# atmega328_programmer_V2.net
KiCad netlist of a schematic drawn in EAGLE
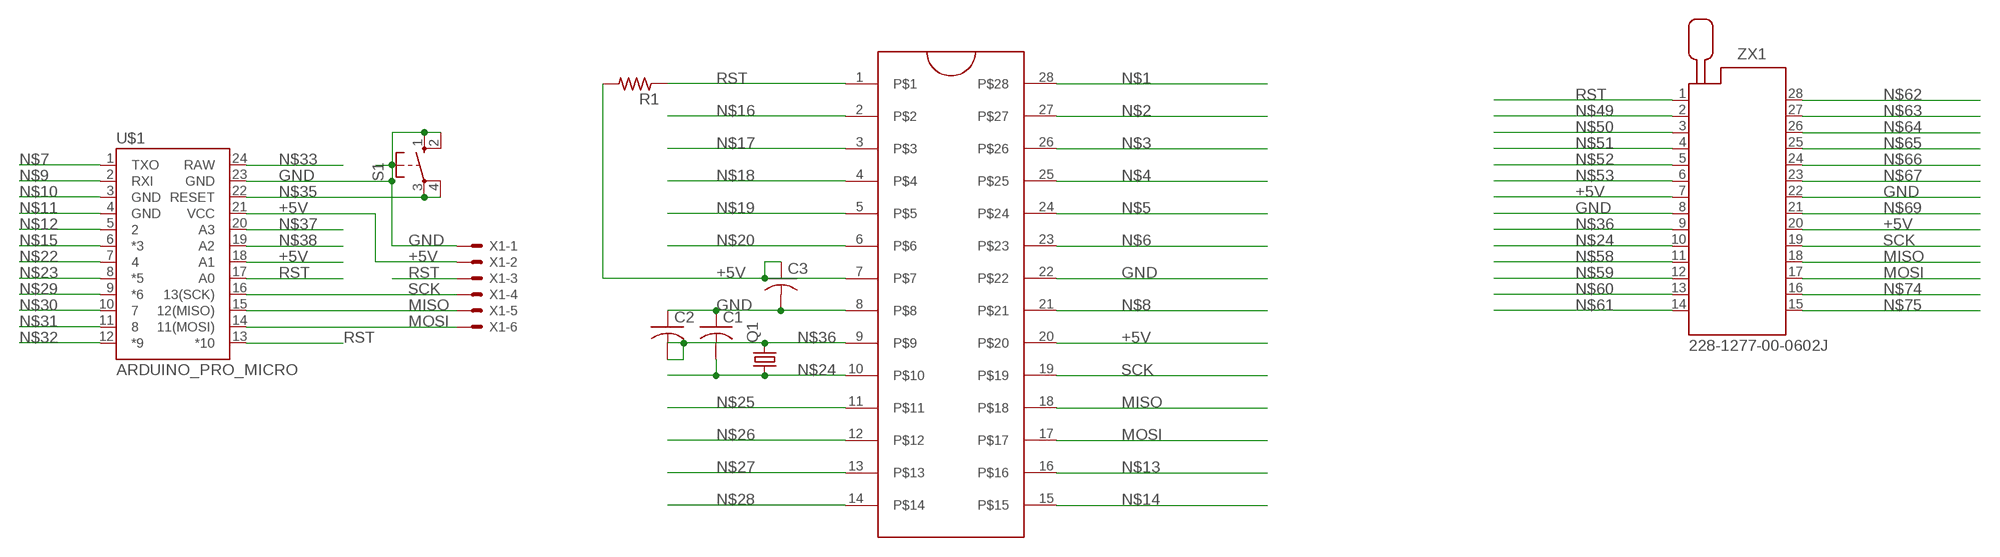
[diagram p0: schematic, sheet 1]

(export (version "E")
  (design (tool "Eeschema 10.0.6"))
  (components
    (comp (ref "C1")
      (value "C-US025-024X044")
      (footprint "eagle-import:C025-024X044")
      (libsource (lib "eagle-import") (part "C-US025-024X044"))
    )
    (comp (ref "C2")
      (value "C-US025-024X044")
      (footprint "eagle-import:C025-024X044")
      (libsource (lib "eagle-import") (part "C-US025-024X044"))
    )
    (comp (ref "C3")
      (value "C-US025-024X044")
      (footprint "eagle-import:C025-024X044")
      (libsource (lib "eagle-import") (part "C-US025-024X044"))
    )
    (comp (ref "Q1")
      (value "CRYSTALHC49U-V")
      (footprint "eagle-import:HC49U-V")
      (libsource (lib "eagle-import") (part "CRYSTALHC49U-V"))
    )
    (comp (ref "R1")
      (value "R-US_0207/10")
      (footprint "eagle-import:0207_10")
      (libsource (lib "eagle-import") (part "R-US_0207/10"))
    )
    (comp (ref "S1")
      (value "10-XX")
      (footprint "eagle-import:B3F-10XX")
      (fields (field (name "MPN") "B3F-1000"))
      (libsource (lib "eagle-import") (part "10-XX"))
    )
    (comp (ref "U$1")
      (value "ARDUINO_PRO_MICRO")
      (footprint "eagle-import:ARDUINO_PRO_MICRO")
      (libsource (lib "eagle-import") (part "ARDUINO_PRO_MICRO"))
    )
    (comp (ref "U$2")
      (value "ZIFSOCKET-28-3ZIFFSOCKET-28-3")
      (footprint "eagle-import:DIL28-3-ZIF_SOCKET")
      (libsource (lib "eagle-import") (part "ZIFSOCKET-28-3ZIFFSOCKET-28-3"))
    )
    (comp (ref "X1")
      (value "22-23-2061")
      (footprint "eagle-import:22-23-2061")
      (fields (field (name "MF") "MOLEX"))
      (libsource (lib "eagle-import") (part "22-23-2061"))
    )
    (comp (ref "ZX1")
      (value "228-1277-00-0602J")
      (footprint "eagle-import:228-1277-00-0602J")
      (fields (field (name "MF") "3M"))
      (libsource (lib "eagle-import") (part "228-?00-0602J1277-"))
    )
  )
  (nets
    (net (code "1") (name "/+5V") (class "Default")
      (node (ref "C3") (pin "1") (pinfunction "1_1") (pintype "passive"))
      (node (ref "R1") (pin "2") (pinfunction "2_2") (pintype "passive"))
      (node (ref "U$1") (pin "18") (pinfunction "A1_18") (pintype "bidirectional"))
      (node (ref "U$1") (pin "21") (pinfunction "VCC_21") (pintype "bidirectional"))
      (node (ref "U$2") (pin "20") (pinfunction "P$20_20") (pintype "bidirectional"))
      (node (ref "U$2") (pin "7") (pinfunction "P$7_7") (pintype "bidirectional"))
      (node (ref "X1") (pin "2") (pinfunction "S_2") (pintype "passive"))
      (node (ref "ZX1") (pin "20") (pinfunction "20_20") (pintype "passive"))
      (node (ref "ZX1") (pin "7") (pinfunction "7_7") (pintype "passive"))
    )
    (net (code "2") (name "/GND") (class "Default")
      (node (ref "C1") (pin "1") (pinfunction "1_1") (pintype "passive"))
      (node (ref "C2") (pin "1") (pinfunction "1_1") (pintype "passive"))
      (node (ref "C3") (pin "2") (pinfunction "2_2") (pintype "passive"))
      (node (ref "S1") (pin "1") (pinfunction "S_1") (pintype "passive"))
      (node (ref "S1") (pin "2") (pinfunction "S1_2") (pintype "passive"))
      (node (ref "U$1") (pin "23") (pinfunction "GND_23") (pintype "bidirectional"))
      (node (ref "U$2") (pin "22") (pinfunction "P$22_22") (pintype "bidirectional"))
      (node (ref "U$2") (pin "8") (pinfunction "P$8_8") (pintype "bidirectional"))
      (node (ref "X1") (pin "1") (pinfunction "S_1") (pintype "passive"))
      (node (ref "ZX1") (pin "22") (pinfunction "22_22") (pintype "passive"))
      (node (ref "ZX1") (pin "8") (pinfunction "8_8") (pintype "passive"))
    )
    (net (code "3") (name "/MISO") (class "Default")
      (node (ref "U$1") (pin "15") (pinfunction "12(MISO)_15") (pintype "bidirectional"))
      (node (ref "U$2") (pin "18") (pinfunction "P$18_18") (pintype "bidirectional"))
      (node (ref "X1") (pin "5") (pinfunction "S_5") (pintype "passive"))
      (node (ref "ZX1") (pin "18") (pinfunction "18_18") (pintype "passive"))
    )
    (net (code "4") (name "/MOSI") (class "Default")
      (node (ref "U$1") (pin "14") (pinfunction "11(MOSI)_14") (pintype "bidirectional"))
      (node (ref "U$2") (pin "17") (pinfunction "P$17_17") (pintype "bidirectional"))
      (node (ref "X1") (pin "6") (pinfunction "S_6") (pintype "passive"))
      (node (ref "ZX1") (pin "17") (pinfunction "17_17") (pintype "passive"))
    )
    (net (code "5") (name "/N$1") (class "Default")
      (node (ref "U$2") (pin "28") (pinfunction "P$28_28") (pintype "bidirectional"))
    )
    (net (code "6") (name "/N$2") (class "Default")
      (node (ref "U$2") (pin "27") (pinfunction "P$27_27") (pintype "bidirectional"))
    )
    (net (code "7") (name "/N$3") (class "Default")
      (node (ref "U$2") (pin "26") (pinfunction "P$26_26") (pintype "bidirectional"))
    )
    (net (code "8") (name "/N$4") (class "Default")
      (node (ref "U$2") (pin "25") (pinfunction "P$25_25") (pintype "bidirectional"))
    )
    (net (code "9") (name "/N$5") (class "Default")
      (node (ref "U$2") (pin "24") (pinfunction "P$24_24") (pintype "bidirectional"))
    )
    (net (code "10") (name "/N$6") (class "Default")
      (node (ref "U$2") (pin "23") (pinfunction "P$23_23") (pintype "bidirectional"))
    )
    (net (code "11") (name "/N$7") (class "Default")
      (node (ref "U$1") (pin "1") (pinfunction "TXO_1") (pintype "bidirectional"))
    )
    (net (code "12") (name "/N$8") (class "Default")
      (node (ref "U$2") (pin "21") (pinfunction "P$21_21") (pintype "bidirectional"))
    )
    (net (code "13") (name "/N$9") (class "Default")
      (node (ref "U$1") (pin "2") (pinfunction "RXI_2") (pintype "bidirectional"))
    )
    (net (code "14") (name "/N$10") (class "Default")
      (node (ref "U$1") (pin "3") (pinfunction "GND_3") (pintype "bidirectional"))
    )
    (net (code "15") (name "/N$11") (class "Default")
      (node (ref "U$1") (pin "4") (pinfunction "GND_4") (pintype "bidirectional"))
    )
    (net (code "16") (name "/N$12") (class "Default")
      (node (ref "U$1") (pin "5") (pinfunction "2_5") (pintype "bidirectional"))
    )
    (net (code "17") (name "/N$13") (class "Default")
      (node (ref "U$2") (pin "16") (pinfunction "P$16_16") (pintype "bidirectional"))
    )
    (net (code "18") (name "/N$14") (class "Default")
      (node (ref "U$2") (pin "15") (pinfunction "P$15_15") (pintype "bidirectional"))
    )
    (net (code "19") (name "/N$15") (class "Default")
      (node (ref "U$1") (pin "6") (pinfunction "*3_6") (pintype "bidirectional"))
    )
    (net (code "20") (name "/N$16") (class "Default")
      (node (ref "U$2") (pin "2") (pinfunction "P$2_2") (pintype "bidirectional"))
    )
    (net (code "21") (name "/N$17") (class "Default")
      (node (ref "U$2") (pin "3") (pinfunction "P$3_3") (pintype "bidirectional"))
    )
    (net (code "22") (name "/N$18") (class "Default")
      (node (ref "U$2") (pin "4") (pinfunction "P$4_4") (pintype "bidirectional"))
    )
    (net (code "23") (name "/N$19") (class "Default")
      (node (ref "U$2") (pin "5") (pinfunction "P$5_5") (pintype "bidirectional"))
    )
    (net (code "24") (name "/N$20") (class "Default")
      (node (ref "U$2") (pin "6") (pinfunction "P$6_6") (pintype "bidirectional"))
    )
    (net (code "25") (name "/N$22") (class "Default")
      (node (ref "U$1") (pin "7") (pinfunction "4_7") (pintype "bidirectional"))
    )
    (net (code "26") (name "/N$23") (class "Default")
      (node (ref "U$1") (pin "8") (pinfunction "*5_8") (pintype "bidirectional"))
    )
    (net (code "27") (name "/N$24") (class "Default")
      (node (ref "C1") (pin "2") (pinfunction "2_2") (pintype "passive"))
      (node (ref "Q1") (pin "1") (pinfunction "1_1") (pintype "passive"))
      (node (ref "U$2") (pin "10") (pinfunction "P$10_10") (pintype "bidirectional"))
      (node (ref "ZX1") (pin "10") (pinfunction "10_10") (pintype "passive"))
    )
    (net (code "28") (name "/N$25") (class "Default")
      (node (ref "U$2") (pin "11") (pinfunction "P$11_11") (pintype "bidirectional"))
    )
    (net (code "29") (name "/N$26") (class "Default")
      (node (ref "U$2") (pin "12") (pinfunction "P$12_12") (pintype "bidirectional"))
    )
    (net (code "30") (name "/N$27") (class "Default")
      (node (ref "U$2") (pin "13") (pinfunction "P$13_13") (pintype "bidirectional"))
    )
    (net (code "31") (name "/N$28") (class "Default")
      (node (ref "U$2") (pin "14") (pinfunction "P$14_14") (pintype "bidirectional"))
    )
    (net (code "32") (name "/N$29") (class "Default")
      (node (ref "U$1") (pin "9") (pinfunction "*6_9") (pintype "bidirectional"))
    )
    (net (code "33") (name "/N$30") (class "Default")
      (node (ref "U$1") (pin "10") (pinfunction "7_10") (pintype "bidirectional"))
    )
    (net (code "34") (name "/N$31") (class "Default")
      (node (ref "U$1") (pin "11") (pinfunction "8_11") (pintype "bidirectional"))
    )
    (net (code "35") (name "/N$32") (class "Default")
      (node (ref "U$1") (pin "12") (pinfunction "*9_12") (pintype "bidirectional"))
    )
    (net (code "36") (name "/N$33") (class "Default")
      (node (ref "U$1") (pin "24") (pinfunction "RAW_24") (pintype "bidirectional"))
    )
    (net (code "37") (name "/N$35") (class "Default")
      (node (ref "S1") (pin "3") (pinfunction "P_3") (pintype "passive"))
      (node (ref "S1") (pin "4") (pinfunction "P1_4") (pintype "passive"))
      (node (ref "U$1") (pin "22") (pinfunction "RESET_22") (pintype "bidirectional"))
    )
    (net (code "38") (name "/N$36") (class "Default")
      (node (ref "C2") (pin "2") (pinfunction "2_2") (pintype "passive"))
      (node (ref "Q1") (pin "2") (pinfunction "2_2") (pintype "passive"))
      (node (ref "U$2") (pin "9") (pinfunction "P$9_9") (pintype "bidirectional"))
      (node (ref "ZX1") (pin "9") (pinfunction "9_9") (pintype "passive"))
    )
    (net (code "39") (name "/N$37") (class "Default")
      (node (ref "U$1") (pin "20") (pinfunction "A3_20") (pintype "bidirectional"))
    )
    (net (code "40") (name "/N$38") (class "Default")
      (node (ref "U$1") (pin "19") (pinfunction "A2_19") (pintype "bidirectional"))
    )
    (net (code "41") (name "/N$49") (class "Default")
      (node (ref "ZX1") (pin "2") (pinfunction "2_2") (pintype "passive"))
    )
    (net (code "42") (name "/N$50") (class "Default")
      (node (ref "ZX1") (pin "3") (pinfunction "3_3") (pintype "passive"))
    )
    (net (code "43") (name "/N$51") (class "Default")
      (node (ref "ZX1") (pin "4") (pinfunction "4_4") (pintype "passive"))
    )
    (net (code "44") (name "/N$52") (class "Default")
      (node (ref "ZX1") (pin "5") (pinfunction "5_5") (pintype "passive"))
    )
    (net (code "45") (name "/N$53") (class "Default")
      (node (ref "ZX1") (pin "6") (pinfunction "6_6") (pintype "passive"))
    )
    (net (code "46") (name "/N$58") (class "Default")
      (node (ref "ZX1") (pin "11") (pinfunction "11_11") (pintype "passive"))
    )
    (net (code "47") (name "/N$59") (class "Default")
      (node (ref "ZX1") (pin "12") (pinfunction "12_12") (pintype "passive"))
    )
    (net (code "48") (name "/N$60") (class "Default")
      (node (ref "ZX1") (pin "13") (pinfunction "13_13") (pintype "passive"))
    )
    (net (code "49") (name "/N$61") (class "Default")
      (node (ref "ZX1") (pin "14") (pinfunction "14_14") (pintype "passive"))
    )
    (net (code "50") (name "/N$62") (class "Default")
      (node (ref "ZX1") (pin "28") (pinfunction "28_28") (pintype "passive"))
    )
    (net (code "51") (name "/N$63") (class "Default")
      (node (ref "ZX1") (pin "27") (pinfunction "27_27") (pintype "passive"))
    )
    (net (code "52") (name "/N$64") (class "Default")
      (node (ref "ZX1") (pin "26") (pinfunction "26_26") (pintype "passive"))
    )
    (net (code "53") (name "/N$65") (class "Default")
      (node (ref "ZX1") (pin "25") (pinfunction "25_25") (pintype "passive"))
    )
    (net (code "54") (name "/N$66") (class "Default")
      (node (ref "ZX1") (pin "24") (pinfunction "24_24") (pintype "passive"))
    )
    (net (code "55") (name "/N$67") (class "Default")
      (node (ref "ZX1") (pin "23") (pinfunction "23_23") (pintype "passive"))
    )
    (net (code "56") (name "/N$69") (class "Default")
      (node (ref "ZX1") (pin "21") (pinfunction "21_21") (pintype "passive"))
    )
    (net (code "57") (name "/N$74") (class "Default")
      (node (ref "ZX1") (pin "16") (pinfunction "16_16") (pintype "passive"))
    )
    (net (code "58") (name "/N$75") (class "Default")
      (node (ref "ZX1") (pin "15") (pinfunction "15_15") (pintype "passive"))
    )
    (net (code "59") (name "/RST") (class "Default")
      (node (ref "R1") (pin "1") (pinfunction "1_1") (pintype "passive"))
      (node (ref "U$1") (pin "13") (pinfunction "*10_13") (pintype "bidirectional"))
      (node (ref "U$1") (pin "17") (pinfunction "A0_17") (pintype "bidirectional"))
      (node (ref "U$2") (pin "1") (pinfunction "P$1_1") (pintype "bidirectional"))
      (node (ref "X1") (pin "3") (pinfunction "S_3") (pintype "passive"))
      (node (ref "ZX1") (pin "1") (pinfunction "1_1") (pintype "passive"))
    )
    (net (code "60") (name "/SCK") (class "Default")
      (node (ref "U$1") (pin "16") (pinfunction "13(SCK)_16") (pintype "bidirectional"))
      (node (ref "U$2") (pin "19") (pinfunction "P$19_19") (pintype "bidirectional"))
      (node (ref "X1") (pin "4") (pinfunction "S_4") (pintype "passive"))
      (node (ref "ZX1") (pin "19") (pinfunction "19_19") (pintype "passive"))
    )
  )
)
